# HIVE_BOARD_ETHERNET.net
KiCad netlist of a schematic drawn in Altium Designer
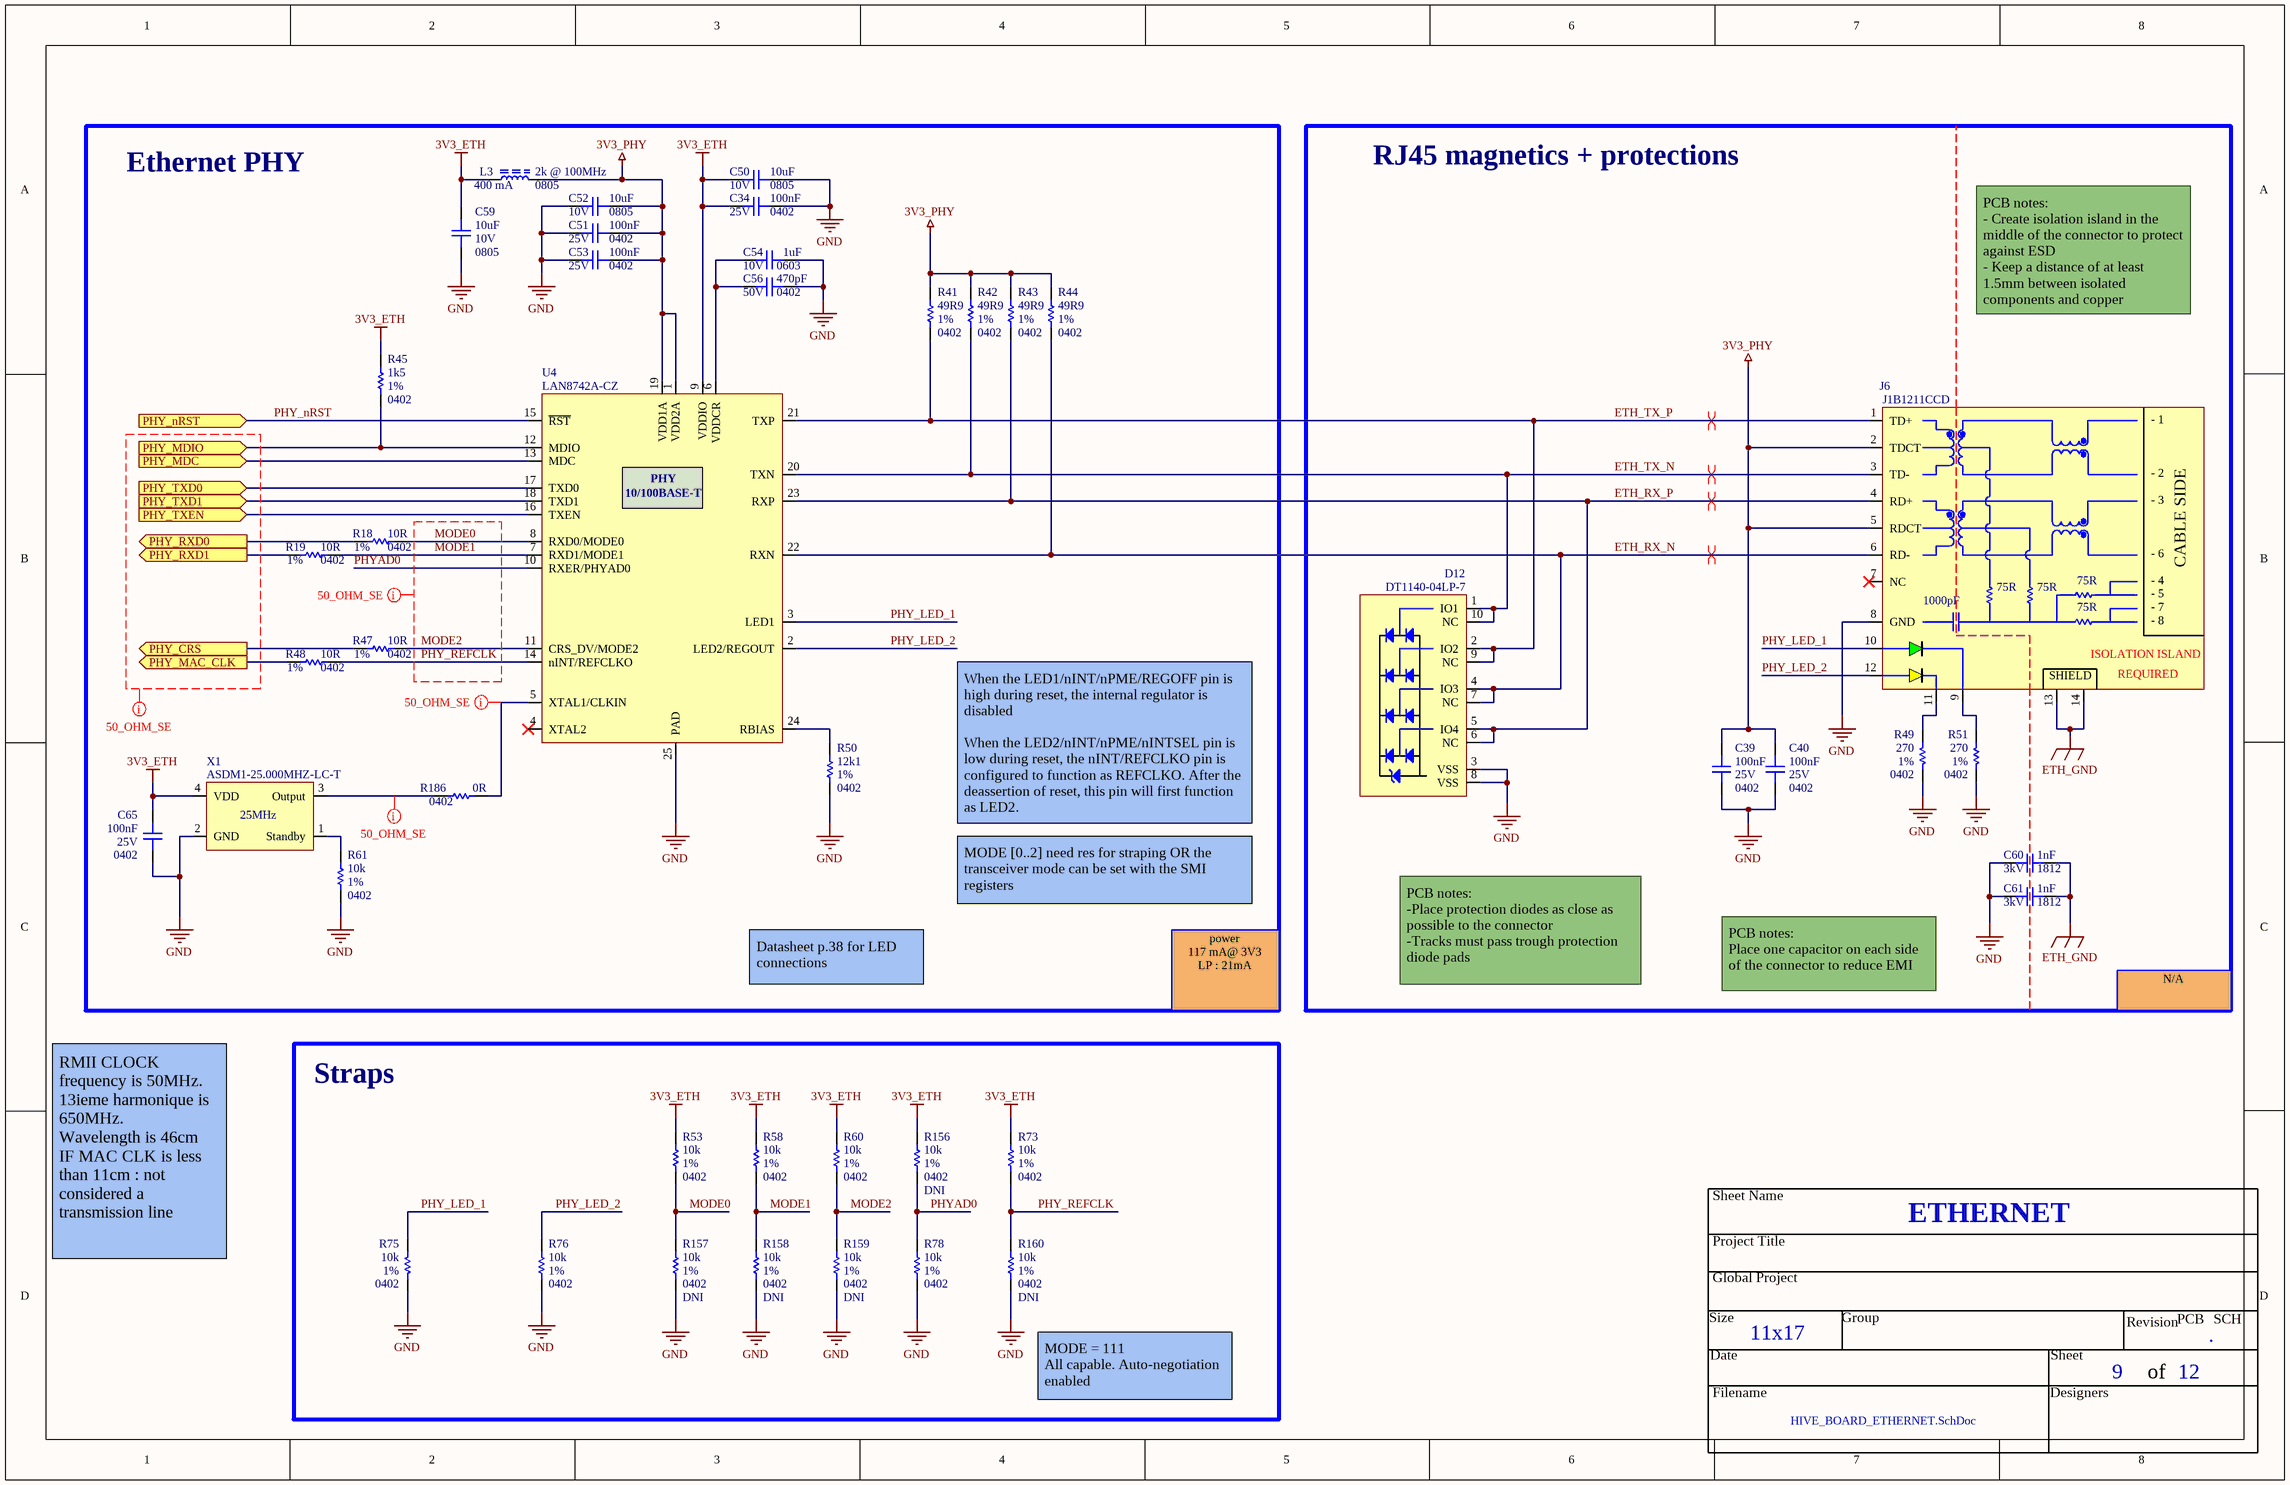
[diagram p0: HIVE_BOARD_ETHERNET.SchDoc]

(export (version "E")
  (design (tool "Eeschema 10.0.6"))
  (components
    (comp (ref "C34")
      (value "100nF")
      (footprint "CAP_CER_0402")
      (description "CAP - CER 0.1µF 10% 25V X7R - 0402")
      (fields
        (field (name "TOLERANCE") "10%")
        (field (name "PACKAGE") "0402")
        (field (name "VOLTAGE RATING") "25V")
        (field (name "Comment") "CGA2B3X7R1E104K050BB")
        (field (name "CREATEDBY/DATE") "Nicolas Roy 2018-11-07")
        (field (name "VERIFIEDBY") "Nicolas V. (2019-01-22)")
      )
      (libsource (lib "GRAMS_MASTER_LIB") (part "CAP_CER_CGA2B3X7R1E104K050BB"))
    )
    (comp (ref "C39")
      (value "100nF")
      (footprint "CAP_CER_0402")
      (description "CAP - CER 0.1µF 10% 25V X7R - 0402")
      (fields
        (field (name "TOLERANCE") "10%")
        (field (name "PACKAGE") "0402")
        (field (name "VOLTAGE RATING") "25V")
        (field (name "Comment") "CGA2B3X7R1E104K050BB")
        (field (name "CREATEDBY/DATE") "Nicolas Roy 2018-11-07")
        (field (name "VERIFIEDBY") "Nicolas V. (2019-01-22)")
      )
      (libsource (lib "GRAMS_MASTER_LIB") (part "CAP_CER_CGA2B3X7R1E104K050BB"))
    )
    (comp (ref "C40")
      (value "100nF")
      (footprint "CAP_CER_0402")
      (description "CAP - CER 0.1µF 10% 25V X7R - 0402")
      (fields
        (field (name "TOLERANCE") "10%")
        (field (name "PACKAGE") "0402")
        (field (name "VOLTAGE RATING") "25V")
        (field (name "Comment") "CGA2B3X7R1E104K050BB")
        (field (name "CREATEDBY/DATE") "Nicolas Roy 2018-11-07")
        (field (name "VERIFIEDBY") "Nicolas V. (2019-01-22)")
      )
      (libsource (lib "GRAMS_MASTER_LIB") (part "CAP_CER_CGA2B3X7R1E104K050BB"))
    )
    (comp (ref "C50")
      (value "10uF")
      (footprint "CAP_CER_0805")
      (description "CAP - CER 10UF 10% 10V X5R - 0805")
      (fields
        (field (name "TOLERANCE") "10%")
        (field (name "PACKAGE") "0805")
        (field (name "VOLTAGE RATING") "10V")
        (field (name "Comment") "LMK212BJ106KG-T")
        (field (name "CREATEDBY/DATE") "Caroline Paulin / 25 juillet 2018")
        (field (name "VERIFIEDBY") "Nicolas V. (2019-01-22)")
      )
      (libsource (lib "GRAMS_MASTER_LIB") (part "CAP_CER_LMK212BJ106KG-T"))
    )
    (comp (ref "C51")
      (value "100nF")
      (footprint "CAP_CER_0402")
      (description "CAP - CER 0.1µF 10% 25V X7R - 0402")
      (fields
        (field (name "TOLERANCE") "10%")
        (field (name "PACKAGE") "0402")
        (field (name "VOLTAGE RATING") "25V")
        (field (name "Comment") "CGA2B3X7R1E104K050BB")
        (field (name "CREATEDBY/DATE") "Nicolas Roy 2018-11-07")
        (field (name "VERIFIEDBY") "Nicolas V. (2019-01-22)")
      )
      (libsource (lib "GRAMS_MASTER_LIB") (part "CAP_CER_CGA2B3X7R1E104K050BB"))
    )
    (comp (ref "C52")
      (value "10uF")
      (footprint "CAP_CER_0805")
      (description "CAP - CER 10UF 10% 10V X5R - 0805")
      (fields
        (field (name "TOLERANCE") "10%")
        (field (name "PACKAGE") "0805")
        (field (name "VOLTAGE RATING") "10V")
        (field (name "Comment") "LMK212BJ106KG-T")
        (field (name "CREATEDBY/DATE") "Caroline Paulin / 25 juillet 2018")
        (field (name "VERIFIEDBY") "Nicolas V. (2019-01-22)")
      )
      (libsource (lib "GRAMS_MASTER_LIB") (part "CAP_CER_LMK212BJ106KG-T"))
    )
    (comp (ref "C53")
      (value "100nF")
      (footprint "CAP_CER_0402")
      (description "CAP - CER 0.1µF 10% 25V X7R - 0402")
      (fields
        (field (name "TOLERANCE") "10%")
        (field (name "PACKAGE") "0402")
        (field (name "VOLTAGE RATING") "25V")
        (field (name "Comment") "CGA2B3X7R1E104K050BB")
        (field (name "CREATEDBY/DATE") "Nicolas Roy 2018-11-07")
        (field (name "VERIFIEDBY") "Nicolas V. (2019-01-22)")
      )
      (libsource (lib "GRAMS_MASTER_LIB") (part "CAP_CER_CGA2B3X7R1E104K050BB"))
    )
    (comp (ref "C54")
      (value "1uF")
      (footprint "CAP_CER_0603")
      (description "CAP - CER 1uF 10V 10% X5R - 0603")
      (fields
        (field (name "TOLERANCE") "10%")
        (field (name "PACKAGE") "0603")
        (field (name "VOLTAGE RATING") "10V")
        (field (name "Comment") "C0603C105K8PACTU")
        (field (name "CREATEDBY/DATE") "Hubert Dube - 21/07/20")
        (field (name "VERIFIEDBY") "Louis-Daniel Gaulin - 21/07/20")
      )
      (libsource (lib "SWARMUS_LIB") (part "CAP_CER_C0603C105K8PACTU"))
    )
    (comp (ref "C56")
      (value "470pF")
      (footprint "CAP_CER_0402")
      (description "CAP - CER 470pF 10% 50V X7R - 0402")
      (fields
        (field (name "TOLERANCE") "10%")
        (field (name "PACKAGE") "0402")
        (field (name "VOLTAGE RATING") "50V")
        (field (name "Comment") "CC0402KRX7R9BB471")
        (field (name "CREATEDBY/DATE") "Nicolas Roy 2018-10-17")
        (field (name "VERIFIEDBY") "Caroline Paulin - 18 janv 2019")
      )
      (libsource (lib "GRAMS_MASTER_LIB") (part "CAP_CER_CC0402KRX7R9BB471"))
    )
    (comp (ref "C59")
      (value "10uF")
      (footprint "CAP_CER_0805")
      (description "CAP - CER 10UF 10% 10V X5R - 0805")
      (fields
        (field (name "TOLERANCE") "10%")
        (field (name "PACKAGE") "0805")
        (field (name "VOLTAGE RATING") "10V")
        (field (name "Comment") "LMK212BJ106KG-T")
        (field (name "CREATEDBY/DATE") "Caroline Paulin / 25 juillet 2018")
        (field (name "VERIFIEDBY") "Nicolas V. (2019-01-22)")
      )
      (libsource (lib "GRAMS_MASTER_LIB") (part "CAP_CER_LMK212BJ106KG-T"))
    )
    (comp (ref "C60")
      (value "1nF")
      (footprint "CAP_CER_1812")
      (description "CAP - CER 1000pF ±10% 3000V X7R")
      (fields
        (field (name "TOLERANCE") "10%")
        (field (name "PACKAGE") "1812")
        (field (name "VOLTAGE RATING") "3kV")
        (field (name "Comment") "885342211009")
        (field (name "CREATEDBY/DATE") "Hubert Dube - 03/02/2021")
        (field (name "VERIFIEDBY") "Philippe Asenault - 08-02-2021")
      )
      (libsource (lib "SWARMUS_LIB") (part "CAP_CER_885342211009"))
    )
    (comp (ref "C61")
      (value "1nF")
      (footprint "CAP_CER_1812")
      (description "CAP - CER 1000pF ±10% 3000V X7R")
      (fields
        (field (name "TOLERANCE") "10%")
        (field (name "PACKAGE") "1812")
        (field (name "VOLTAGE RATING") "3kV")
        (field (name "Comment") "885342211009")
        (field (name "CREATEDBY/DATE") "Hubert Dube - 03/02/2021")
        (field (name "VERIFIEDBY") "Philippe Asenault - 08-02-2021")
      )
      (libsource (lib "SWARMUS_LIB") (part "CAP_CER_885342211009"))
    )
    (comp (ref "C65")
      (value "100nF")
      (footprint "CAP_CER_0402")
      (description "CAP - CER 0.1µF 10% 25V X7R - 0402")
      (fields
        (field (name "TOLERANCE") "10%")
        (field (name "PACKAGE") "0402")
        (field (name "VOLTAGE RATING") "25V")
        (field (name "Comment") "CGA2B3X7R1E104K050BB")
        (field (name "CREATEDBY/DATE") "Nicolas Roy 2018-11-07")
        (field (name "VERIFIEDBY") "Nicolas V. (2019-01-22)")
      )
      (libsource (lib "GRAMS_MASTER_LIB") (part "CAP_CER_CGA2B3X7R1E104K050BB"))
    )
    (comp (ref "D12")
      (value "DT1140-04LP-7")
      (footprint "TVS_DATA_DT1140-04LP-7")
      (description "TVS - DIODE 5.5V 10V - 10-UFDFN")
      (fields
        (field (name "CREATEDBY/DATE") "Joël Lemay 2019-11-20")
        (field (name "VERIFIEDBY") "C.Paulin - 21/11/2019")
      )
      (libsource (lib "GRAMS_MASTER_LIB") (part "TVS_DATA_DT1140-04LP-7"))
    )
    (comp (ref "J6")
      (value "J1B1211CCD")
      (footprint "CON_ETH_J1B1211CCD_WIZ")
      (fields
        (field (name "CREATEDBY/DATE") "Hubert Dube - 12/02/2021")
        (field (name "VERIFIEDBY") "Philippe Arsenault - 2021-03-10")
      )
      (libsource (lib "SWARMUS_LIB") (part "CON_ETH_J1B1211CCD"))
    )
    (comp (ref "L3")
      (value "2k @ 100MHz")
      (footprint "FER_0805")
      (description "FER - FERRITE BEAD 2 KOHM @ 100 MHz 400 mA - 0805")
      (fields
        (field (name "CURRENT RATING") "400 mA")
        (field (name "PACKAGE") "0805")
        (field (name "Comment") "MMZ2012Y202BT000")
        (field (name "CREATEDBY/DATE") "Hubert Dube - 7/02/2021")
        (field (name "VERIFIEDBY") "Philippe Arsenault/ 2021-03-13")
      )
      (libsource (lib "SWARMUS_LIB") (part "FER_MMZ2012Y202BT000"))
    )
    (comp (ref "R18")
      (value "10R")
      (footprint "RES_0402")
      (description "RES - 10R 1% 1/16W - 0402")
      (fields
        (field (name "TOLERANCE") "1%")
        (field (name "PACKAGE") "0402")
        (field (name "Comment") "RMCF0402FT10R0")
        (field (name "CREATEDBY/DATE") "Joel Lemay 2018-07-04")
        (field (name "VERIFIEDBY") "Caroline Paulin - 6 sept 2018")
      )
      (libsource (lib "GRAMS_MASTER_LIB") (part "RES_RMCF0402FT10R0"))
    )
    (comp (ref "R19")
      (value "10R")
      (footprint "RES_0402")
      (description "RES - 10R 1% 1/16W - 0402")
      (fields
        (field (name "TOLERANCE") "1%")
        (field (name "PACKAGE") "0402")
        (field (name "Comment") "RMCF0402FT10R0")
        (field (name "CREATEDBY/DATE") "Joel Lemay 2018-07-04")
        (field (name "VERIFIEDBY") "Caroline Paulin - 6 sept 2018")
      )
      (libsource (lib "GRAMS_MASTER_LIB") (part "RES_RMCF0402FT10R0"))
    )
    (comp (ref "R41")
      (value "49R9")
      (footprint "RES_0402")
      (description "RES - 49.9 R ±1% 1/16W -  0402")
      (fields
        (field (name "TOLERANCE") "1%")
        (field (name "PACKAGE") "0402")
        (field (name "Comment") "RC0402FR-0749R9L")
        (field (name "CREATEDBY/DATE") "Hubert Dubé - 3/02/2020")
        (field (name "VERIFIEDBY") "Philippe Arsenault/2021-02-08")
      )
      (libsource (lib "SWARMUS_LIB") (part "RES_RC0402FR-0749R9L"))
    )
    (comp (ref "R42")
      (value "49R9")
      (footprint "RES_0402")
      (description "RES - 49.9 R ±1% 1/16W -  0402")
      (fields
        (field (name "TOLERANCE") "1%")
        (field (name "PACKAGE") "0402")
        (field (name "Comment") "RC0402FR-0749R9L")
        (field (name "CREATEDBY/DATE") "Hubert Dubé - 3/02/2020")
        (field (name "VERIFIEDBY") "Philippe Arsenault/2021-02-08")
      )
      (libsource (lib "SWARMUS_LIB") (part "RES_RC0402FR-0749R9L"))
    )
    (comp (ref "R43")
      (value "49R9")
      (footprint "RES_0402")
      (description "RES - 49.9 R ±1% 1/16W -  0402")
      (fields
        (field (name "TOLERANCE") "1%")
        (field (name "PACKAGE") "0402")
        (field (name "Comment") "RC0402FR-0749R9L")
        (field (name "CREATEDBY/DATE") "Hubert Dubé - 3/02/2020")
        (field (name "VERIFIEDBY") "Philippe Arsenault/2021-02-08")
      )
      (libsource (lib "SWARMUS_LIB") (part "RES_RC0402FR-0749R9L"))
    )
    (comp (ref "R44")
      (value "49R9")
      (footprint "RES_0402")
      (description "RES - 49.9 R ±1% 1/16W -  0402")
      (fields
        (field (name "TOLERANCE") "1%")
        (field (name "PACKAGE") "0402")
        (field (name "Comment") "RC0402FR-0749R9L")
        (field (name "CREATEDBY/DATE") "Hubert Dubé - 3/02/2020")
        (field (name "VERIFIEDBY") "Philippe Arsenault/2021-02-08")
      )
      (libsource (lib "SWARMUS_LIB") (part "RES_RC0402FR-0749R9L"))
    )
    (comp (ref "R45")
      (value "1k5")
      (footprint "RES_0402")
      (description "RES - 1.5K 1% 1/16W - 0402")
      (fields
        (field (name "TOLERANCE") "1%")
        (field (name "PACKAGE") "0402")
        (field (name "Comment") "RC0402FR-071K5L")
        (field (name "CREATEDBY/DATE") "Philippe Arsenault/21 Janvier 2020")
        (field (name "VERIFIEDBY") "C.Paulin - 28/01/2020")
      )
      (libsource (lib "GRAMS_MASTER_LIB") (part "RES_RC0402FR-071K5L"))
    )
    (comp (ref "R47")
      (value "10R")
      (footprint "RES_0402")
      (description "RES - 10R 1% 1/16W - 0402")
      (fields
        (field (name "TOLERANCE") "1%")
        (field (name "PACKAGE") "0402")
        (field (name "Comment") "RMCF0402FT10R0")
        (field (name "CREATEDBY/DATE") "Joel Lemay 2018-07-04")
        (field (name "VERIFIEDBY") "Caroline Paulin - 6 sept 2018")
      )
      (libsource (lib "GRAMS_MASTER_LIB") (part "RES_RMCF0402FT10R0"))
    )
    (comp (ref "R48")
      (value "10R")
      (footprint "RES_0402")
      (description "RES - 10R 1% 1/16W - 0402")
      (fields
        (field (name "TOLERANCE") "1%")
        (field (name "PACKAGE") "0402")
        (field (name "Comment") "RMCF0402FT10R0")
        (field (name "CREATEDBY/DATE") "Joel Lemay 2018-07-04")
        (field (name "VERIFIEDBY") "Caroline Paulin - 6 sept 2018")
      )
      (libsource (lib "GRAMS_MASTER_LIB") (part "RES_RMCF0402FT10R0"))
    )
    (comp (ref "R49")
      (value "270")
      (footprint "FER_0402")
      (description "RES - 270R 1% 1/16W - 0402")
      (fields
        (field (name "TOLERANCE") "1%")
        (field (name "PACKAGE") "0402")
        (field (name "Comment") "RC0402FR-07270RL")
        (field (name "CREATEDBY/DATE") "Philippe Arsenault 2020-07-24")
        (field (name "VERIFIEDBY") "Louis-Daniel Gaulin / 03-10-2020")
      )
      (libsource (lib "SWARMUS_LIB") (part "RES_RC0402FR-07270RL"))
    )
    (comp (ref "R50")
      (value "12k1")
      (footprint "RES_0402")
      (description "RES - 12K1 ±1% 1/16W - 0402")
      (fields
        (field (name "TOLERANCE") "1%")
        (field (name "PACKAGE") "0402")
        (field (name "Comment") "RC0402FR-0712K1L")
        (field (name "CREATEDBY/DATE") "Hubert Dubé - 7/02/2020")
        (field (name "VERIFIEDBY") "Philippe Arsenault/2021-02-08")
      )
      (libsource (lib "SWARMUS_LIB") (part "RES_RC0402FR-0712K1L"))
    )
    (comp (ref "R51")
      (value "270")
      (footprint "FER_0402")
      (description "RES - 270R 1% 1/16W - 0402")
      (fields
        (field (name "TOLERANCE") "1%")
        (field (name "PACKAGE") "0402")
        (field (name "Comment") "RC0402FR-07270RL")
        (field (name "CREATEDBY/DATE") "Philippe Arsenault 2020-07-24")
        (field (name "VERIFIEDBY") "Louis-Daniel Gaulin / 03-10-2020")
      )
      (libsource (lib "SWARMUS_LIB") (part "RES_RC0402FR-07270RL"))
    )
    (comp (ref "R53")
      (value "10k")
      (footprint "RES_0402")
      (description "RES - 10K OHMS 1% 1/16W - 0402")
      (fields
        (field (name "TOLERANCE") "1%")
        (field (name "PACKAGE") "0402")
        (field (name "Comment") "RC0402FR-0710KL")
        (field (name "CREATEDBY/DATE") "Nicolas V. (2018-11-20)")
        (field (name "VERIFIEDBY") "Nicolas V. (2018-11-20)")
      )
      (libsource (lib "GRAMS_MASTER_LIB") (part "RES_RC0402FR-0710KL"))
    )
    (comp (ref "R58")
      (value "10k")
      (footprint "RES_0402")
      (description "RES - 10K OHMS 1% 1/16W - 0402")
      (fields
        (field (name "TOLERANCE") "1%")
        (field (name "PACKAGE") "0402")
        (field (name "Comment") "RC0402FR-0710KL")
        (field (name "CREATEDBY/DATE") "Nicolas V. (2018-11-20)")
        (field (name "VERIFIEDBY") "Nicolas V. (2018-11-20)")
      )
      (libsource (lib "GRAMS_MASTER_LIB") (part "RES_RC0402FR-0710KL"))
    )
    (comp (ref "R60")
      (value "10k")
      (footprint "RES_0402")
      (description "RES - 10K OHMS 1% 1/16W - 0402")
      (fields
        (field (name "TOLERANCE") "1%")
        (field (name "PACKAGE") "0402")
        (field (name "Comment") "RC0402FR-0710KL")
        (field (name "CREATEDBY/DATE") "Nicolas V. (2018-11-20)")
        (field (name "VERIFIEDBY") "Nicolas V. (2018-11-20)")
      )
      (libsource (lib "GRAMS_MASTER_LIB") (part "RES_RC0402FR-0710KL"))
    )
    (comp (ref "R61")
      (value "10k")
      (footprint "RES_0402")
      (description "RES - 10K OHMS 1% 1/16W - 0402")
      (fields
        (field (name "TOLERANCE") "1%")
        (field (name "PACKAGE") "0402")
        (field (name "Comment") "RC0402FR-0710KL")
        (field (name "CREATEDBY/DATE") "Nicolas V. (2018-11-20)")
        (field (name "VERIFIEDBY") "Nicolas V. (2018-11-20)")
      )
      (libsource (lib "GRAMS_MASTER_LIB") (part "RES_RC0402FR-0710KL"))
    )
    (comp (ref "R73")
      (value "10k")
      (footprint "RES_0402")
      (description "RES - 10K OHMS 1% 1/16W - 0402")
      (fields
        (field (name "TOLERANCE") "1%")
        (field (name "PACKAGE") "0402")
        (field (name "Comment") "RC0402FR-0710KL")
        (field (name "CREATEDBY/DATE") "Nicolas V. (2018-11-20)")
        (field (name "VERIFIEDBY") "Nicolas V. (2018-11-20)")
      )
      (libsource (lib "GRAMS_MASTER_LIB") (part "RES_RC0402FR-0710KL"))
    )
    (comp (ref "R75")
      (value "10k")
      (footprint "RES_0402")
      (description "RES - 10K OHMS 1% 1/16W - 0402")
      (fields
        (field (name "TOLERANCE") "1%")
        (field (name "PACKAGE") "0402")
        (field (name "Comment") "RC0402FR-0710KL")
        (field (name "CREATEDBY/DATE") "Nicolas V. (2018-11-20)")
        (field (name "VERIFIEDBY") "Nicolas V. (2018-11-20)")
      )
      (libsource (lib "GRAMS_MASTER_LIB") (part "RES_RC0402FR-0710KL"))
    )
    (comp (ref "R76")
      (value "10k")
      (footprint "RES_0402")
      (description "RES - 10K OHMS 1% 1/16W - 0402")
      (fields
        (field (name "TOLERANCE") "1%")
        (field (name "PACKAGE") "0402")
        (field (name "Comment") "RC0402FR-0710KL")
        (field (name "CREATEDBY/DATE") "Nicolas V. (2018-11-20)")
        (field (name "VERIFIEDBY") "Nicolas V. (2018-11-20)")
      )
      (libsource (lib "GRAMS_MASTER_LIB") (part "RES_RC0402FR-0710KL"))
    )
    (comp (ref "R78")
      (value "10k")
      (footprint "RES_0402")
      (description "RES - 10K OHMS 1% 1/16W - 0402")
      (fields
        (field (name "TOLERANCE") "1%")
        (field (name "PACKAGE") "0402")
        (field (name "Comment") "RC0402FR-0710KL")
        (field (name "CREATEDBY/DATE") "Nicolas V. (2018-11-20)")
        (field (name "VERIFIEDBY") "Nicolas V. (2018-11-20)")
      )
      (libsource (lib "GRAMS_MASTER_LIB") (part "RES_RC0402FR-0710KL"))
    )
    (comp (ref "R156")
      (value "10k")
      (footprint "RES_0402")
      (description "RES - 10K OHMS 1% 1/16W - 0402")
      (fields
        (field (name "TOLERANCE") "1%")
        (field (name "ASSEMBLY NOTE") "DNI")
        (field (name "PACKAGE") "0402")
        (field (name "Comment") "RC0402FR-0710KL")
        (field (name "CREATEDBY/DATE") "Nicolas V. (2018-11-20)")
        (field (name "VERIFIEDBY") "Nicolas V. (2018-11-20)")
      )
      (libsource (lib "GRAMS_MASTER_LIB") (part "RES_RC0402FR-0710KL"))
    )
    (comp (ref "R157")
      (value "10k")
      (footprint "RES_0402")
      (description "RES - 10K OHMS 1% 1/16W - 0402")
      (fields
        (field (name "TOLERANCE") "1%")
        (field (name "ASSEMBLY NOTE") "DNI")
        (field (name "PACKAGE") "0402")
        (field (name "Comment") "RC0402FR-0710KL")
        (field (name "CREATEDBY/DATE") "Nicolas V. (2018-11-20)")
        (field (name "VERIFIEDBY") "Nicolas V. (2018-11-20)")
      )
      (libsource (lib "GRAMS_MASTER_LIB") (part "RES_RC0402FR-0710KL"))
    )
    (comp (ref "R158")
      (value "10k")
      (footprint "RES_0402")
      (description "RES - 10K OHMS 1% 1/16W - 0402")
      (fields
        (field (name "TOLERANCE") "1%")
        (field (name "ASSEMBLY NOTE") "DNI")
        (field (name "PACKAGE") "0402")
        (field (name "Comment") "RC0402FR-0710KL")
        (field (name "CREATEDBY/DATE") "Nicolas V. (2018-11-20)")
        (field (name "VERIFIEDBY") "Nicolas V. (2018-11-20)")
      )
      (libsource (lib "GRAMS_MASTER_LIB") (part "RES_RC0402FR-0710KL"))
    )
    (comp (ref "R159")
      (value "10k")
      (footprint "RES_0402")
      (description "RES - 10K OHMS 1% 1/16W - 0402")
      (fields
        (field (name "TOLERANCE") "1%")
        (field (name "ASSEMBLY NOTE") "DNI")
        (field (name "PACKAGE") "0402")
        (field (name "Comment") "RC0402FR-0710KL")
        (field (name "CREATEDBY/DATE") "Nicolas V. (2018-11-20)")
        (field (name "VERIFIEDBY") "Nicolas V. (2018-11-20)")
      )
      (libsource (lib "GRAMS_MASTER_LIB") (part "RES_RC0402FR-0710KL"))
    )
    (comp (ref "R160")
      (value "10k")
      (footprint "RES_0402")
      (description "RES - 10K OHMS 1% 1/16W - 0402")
      (fields
        (field (name "TOLERANCE") "1%")
        (field (name "ASSEMBLY NOTE") "DNI")
        (field (name "PACKAGE") "0402")
        (field (name "Comment") "RC0402FR-0710KL")
        (field (name "CREATEDBY/DATE") "Nicolas V. (2018-11-20)")
        (field (name "VERIFIEDBY") "Nicolas V. (2018-11-20)")
      )
      (libsource (lib "GRAMS_MASTER_LIB") (part "RES_RC0402FR-0710KL"))
    )
    (comp (ref "R186")
      (value "0R")
      (footprint "RES_0402")
      (description "RES - 0R 1/16W 1A  - 0402")
      (fields
        (field (name "PACKAGE") "0402")
        (field (name "Comment") "RC0402FR-070RL")
        (field (name "CREATEDBY/DATE") "Keven Deslandes 2018-09-12")
        (field (name "VERIFIEDBY") "Caroline Paulin - 27 fév 2019")
      )
      (libsource (lib "GRAMS_MASTER_LIB") (part "RES_RC0402FR-070RL"))
    )
    (comp (ref "U4")
      (value "LAN8742A-CZ")
      (footprint "COM_ETH_LAN8742A-CZ-TR")
      (description "COM_ETH_ Ethernet PHY 1/1 Transceiver  Ethernet 24-SQFN (4x4) 10/100 BASE-T")
      (fields
        (field (name "VERIFIEDBY") "Philippe Arsenault 2021-03-10")
        (field (name "CREATEDBY/DATE") "Hubert Dube -  28/01/2021")
      )
      (libsource (lib "SWARMUS_LIB") (part "COM_ETH_LAN8742A-CZ"))
    )
    (comp (ref "X1")
      (value "ASDM1-25.000MHZ-LC-T")
      (footprint "OSC_CRY_ASDM1-25.000MHZ-LC-T")
      (description "OSC_CRY - 25MHz +-50ppm LVCMOS Crystal")
      (fields
        (field (name "CREATEDBY/DATE") "Philippe Arsenault/2021-04-07")
        (field (name "VERIFIEDBY") "Louis-Daniel Gaulin / 08-04-2021")
      )
      (libsource (lib "SWARMUS_LIB") (part "OSC_CRY_ASDM1-25.000MHZ-LC-T"))
    )
  )
  (nets
    (net (code "1") (name "/ETH_RX_N") (class "Default")
      (node (ref "D12") (pin "4") (pinfunction "IO3_4") (pintype "passive"))
      (node (ref "D12") (pin "7") (pinfunction "NC_7") (pintype "passive"))
      (node (ref "J6") (pin "6") (pinfunction "RD-_6") (pintype "passive"))
      (node (ref "R44") (pin "1") (pinfunction "1_1") (pintype "passive"))
      (node (ref "U4") (pin "22") (pinfunction "RXN_22") (pintype "passive"))
    )
    (net (code "2") (name "/ETH_RX_P") (class "Default")
      (node (ref "D12") (pin "5") (pinfunction "IO4_5") (pintype "passive"))
      (node (ref "D12") (pin "6") (pinfunction "NC_6") (pintype "passive"))
      (node (ref "J6") (pin "4") (pinfunction "RD+_4") (pintype "passive"))
      (node (ref "R43") (pin "1") (pinfunction "1_1") (pintype "passive"))
      (node (ref "U4") (pin "23") (pinfunction "RXP_23") (pintype "passive"))
    )
    (net (code "3") (name "/ETH_TX_N") (class "Default")
      (node (ref "D12") (pin "1") (pinfunction "IO1_1") (pintype "passive"))
      (node (ref "D12") (pin "10") (pinfunction "NC_10") (pintype "passive"))
      (node (ref "J6") (pin "3") (pinfunction "TD-_3") (pintype "passive"))
      (node (ref "R42") (pin "1") (pinfunction "1_1") (pintype "passive"))
      (node (ref "U4") (pin "20") (pinfunction "TXN_20") (pintype "passive"))
    )
    (net (code "4") (name "/ETH_TX_P") (class "Default")
      (node (ref "D12") (pin "2") (pinfunction "IO2_2") (pintype "passive"))
      (node (ref "D12") (pin "9") (pinfunction "NC_9") (pintype "passive"))
      (node (ref "J6") (pin "1") (pinfunction "TD+_1") (pintype "passive"))
      (node (ref "R41") (pin "1") (pinfunction "1_1") (pintype "passive"))
      (node (ref "U4") (pin "21") (pinfunction "TXP_21") (pintype "passive"))
    )
    (net (code "5") (name "/MODE0") (class "Default")
      (node (ref "R157") (pin "2") (pinfunction "2_2") (pintype "passive"))
      (node (ref "R18") (pin "1") (pinfunction "1_1") (pintype "passive"))
      (node (ref "R53") (pin "1") (pinfunction "1_1") (pintype "passive"))
      (node (ref "U4") (pin "8") (pinfunction "RXD0/MODE0_8") (pintype "passive"))
    )
    (net (code "6") (name "/MODE1") (class "Default")
      (node (ref "R158") (pin "2") (pinfunction "2_2") (pintype "passive"))
      (node (ref "R19") (pin "1") (pinfunction "1_1") (pintype "passive"))
      (node (ref "R58") (pin "1") (pinfunction "1_1") (pintype "passive"))
      (node (ref "U4") (pin "7") (pinfunction "RXD1/MODE1_7") (pintype "passive"))
    )
    (net (code "7") (name "/MODE2") (class "Default")
      (node (ref "R159") (pin "2") (pinfunction "2_2") (pintype "passive"))
      (node (ref "R47") (pin "1") (pinfunction "1_1") (pintype "passive"))
      (node (ref "R60") (pin "1") (pinfunction "1_1") (pintype "passive"))
      (node (ref "U4") (pin "11") (pinfunction "CRS_DV/MODE2_11") (pintype "passive"))
    )
    (net (code "8") (name "/PHYAD0") (class "Default")
      (node (ref "R156") (pin "1") (pinfunction "1_1") (pintype "passive"))
      (node (ref "R78") (pin "2") (pinfunction "2_2") (pintype "passive"))
      (node (ref "U4") (pin "10") (pinfunction "RXER/PHYAD0_10") (pintype "passive"))
    )
    (net (code "9") (name "/PHY_CRS") (class "Default")
      (node (ref "R47") (pin "2") (pinfunction "2_2") (pintype "passive"))
    )
    (net (code "10") (name "/PHY_LED_1") (class "Default")
      (node (ref "J6") (pin "10") (pinfunction "LED1_A_10") (pintype "passive"))
      (node (ref "R75") (pin "2") (pinfunction "2_2") (pintype "passive"))
      (node (ref "U4") (pin "3") (pinfunction "LED1_3") (pintype "passive"))
    )
    (net (code "11") (name "/PHY_LED_2") (class "Default")
      (node (ref "J6") (pin "12") (pintype "passive"))
      (node (ref "R76") (pin "2") (pinfunction "2_2") (pintype "passive"))
      (node (ref "U4") (pin "2") (pinfunction "LED2/REGOUT_2") (pintype "passive"))
    )
    (net (code "12") (name "/PHY_MAC_CLK") (class "Default")
      (node (ref "R48") (pin "2") (pinfunction "2_2") (pintype "passive"))
    )
    (net (code "13") (name "/PHY_MDC") (class "Default")
      (node (ref "U4") (pin "13") (pinfunction "MDC_13") (pintype "passive"))
    )
    (net (code "14") (name "/PHY_MDIO") (class "Default")
      (node (ref "R45") (pin "1") (pinfunction "1_1") (pintype "passive"))
      (node (ref "U4") (pin "12") (pinfunction "MDIO_12") (pintype "passive"))
    )
    (net (code "15") (name "/PHY_REFCLK") (class "Default")
      (node (ref "R160") (pin "2") (pinfunction "2_2") (pintype "passive"))
      (node (ref "R48") (pin "1") (pinfunction "1_1") (pintype "passive"))
      (node (ref "R73") (pin "1") (pinfunction "1_1") (pintype "passive"))
      (node (ref "U4") (pin "14") (pinfunction "nINT/REFCLKO_14") (pintype "passive"))
    )
    (net (code "16") (name "/PHY_RXD0") (class "Default")
      (node (ref "R18") (pin "2") (pinfunction "2_2") (pintype "passive"))
    )
    (net (code "17") (name "/PHY_RXD1") (class "Default")
      (node (ref "R19") (pin "2") (pinfunction "2_2") (pintype "passive"))
    )
    (net (code "18") (name "/PHY_TXD0") (class "Default")
      (node (ref "U4") (pin "17") (pinfunction "TXD0_17") (pintype "passive"))
    )
    (net (code "19") (name "/PHY_TXD1") (class "Default")
      (node (ref "U4") (pin "18") (pinfunction "TXD1_18") (pintype "passive"))
    )
    (net (code "20") (name "/PHY_TXEN") (class "Default")
      (node (ref "U4") (pin "16") (pinfunction "TXEN_16") (pintype "passive"))
    )
    (net (code "21") (name "/PHY_nRST") (class "Default")
      (node (ref "U4") (pin "15") (pinfunction "RST_15") (pintype "passive"))
    )
    (net (code "22") (name "3V3_ETH") (class "Default")
      (node (ref "C34") (pin "2") (pinfunction "2_2") (pintype "passive"))
      (node (ref "C50") (pin "2") (pinfunction "2_2") (pintype "passive"))
      (node (ref "C59") (pin "2") (pinfunction "2_2") (pintype "passive"))
      (node (ref "C65") (pin "1") (pinfunction "1_1") (pintype "passive"))
      (node (ref "L3") (pin "1") (pinfunction "1_1") (pintype "passive"))
      (node (ref "R156") (pin "2") (pinfunction "2_2") (pintype "passive"))
      (node (ref "R45") (pin "2") (pinfunction "2_2") (pintype "passive"))
      (node (ref "R53") (pin "2") (pinfunction "2_2") (pintype "passive"))
      (node (ref "R58") (pin "2") (pinfunction "2_2") (pintype "passive"))
      (node (ref "R60") (pin "2") (pinfunction "2_2") (pintype "passive"))
      (node (ref "R73") (pin "2") (pinfunction "2_2") (pintype "passive"))
      (node (ref "U4") (pin "9") (pinfunction "VDDIO_9") (pintype "passive"))
      (node (ref "X1") (pin "4") (pinfunction "VDD_4") (pintype "passive"))
    )
    (net (code "23") (name "3V3_PHY") (class "Default")
      (node (ref "C39") (pin "1") (pinfunction "1_1") (pintype "passive"))
      (node (ref "C40") (pin "1") (pinfunction "1_1") (pintype "passive"))
      (node (ref "C51") (pin "1") (pinfunction "1_1") (pintype "passive"))
      (node (ref "C52") (pin "1") (pinfunction "1_1") (pintype "passive"))
      (node (ref "C53") (pin "1") (pinfunction "1_1") (pintype "passive"))
      (node (ref "J6") (pin "2") (pinfunction "TDCT_2") (pintype "passive"))
      (node (ref "J6") (pin "5") (pinfunction "RDCT_5") (pintype "passive"))
      (node (ref "L3") (pin "2") (pinfunction "2_2") (pintype "passive"))
      (node (ref "R41") (pin "2") (pinfunction "2_2") (pintype "passive"))
      (node (ref "R42") (pin "2") (pinfunction "2_2") (pintype "passive"))
      (node (ref "R43") (pin "2") (pinfunction "2_2") (pintype "passive"))
      (node (ref "R44") (pin "2") (pinfunction "2_2") (pintype "passive"))
      (node (ref "U4") (pin "1") (pinfunction "VDD2A_1") (pintype "passive"))
      (node (ref "U4") (pin "19") (pinfunction "VDD1A_19") (pintype "passive"))
    )
    (net (code "24") (name "ETH_GND") (class "Default")
      (node (ref "C60") (pin "1") (pinfunction "1_1") (pintype "passive"))
      (node (ref "C61") (pin "1") (pinfunction "1_1") (pintype "passive"))
      (node (ref "J6") (pin "13") (pinfunction "SHIELD_13") (pintype "passive"))
      (node (ref "J6") (pin "14") (pintype "passive"))
    )
    (net (code "25") (name "GND") (class "Default")
      (node (ref "C34") (pin "1") (pinfunction "1_1") (pintype "passive"))
      (node (ref "C39") (pin "2") (pinfunction "2_2") (pintype "passive"))
      (node (ref "C40") (pin "2") (pinfunction "2_2") (pintype "passive"))
      (node (ref "C50") (pin "1") (pinfunction "1_1") (pintype "passive"))
      (node (ref "C51") (pin "2") (pinfunction "2_2") (pintype "passive"))
      (node (ref "C52") (pin "2") (pinfunction "2_2") (pintype "passive"))
      (node (ref "C53") (pin "2") (pinfunction "2_2") (pintype "passive"))
      (node (ref "C54") (pin "1") (pinfunction "1_1") (pintype "passive"))
      (node (ref "C56") (pin "1") (pinfunction "1_1") (pintype "passive"))
      (node (ref "C59") (pin "1") (pinfunction "1_1") (pintype "passive"))
      (node (ref "C60") (pin "2") (pinfunction "2_2") (pintype "passive"))
      (node (ref "C61") (pin "2") (pinfunction "2_2") (pintype "passive"))
      (node (ref "C65") (pin "2") (pinfunction "2_2") (pintype "passive"))
      (node (ref "D12") (pin "3") (pinfunction "VSS_3") (pintype "passive"))
      (node (ref "D12") (pin "8") (pinfunction "VSS_8") (pintype "passive"))
      (node (ref "J6") (pin "8") (pinfunction "GND_8") (pintype "passive"))
      (node (ref "R157") (pin "1") (pinfunction "1_1") (pintype "passive"))
      (node (ref "R158") (pin "1") (pinfunction "1_1") (pintype "passive"))
      (node (ref "R159") (pin "1") (pinfunction "1_1") (pintype "passive"))
      (node (ref "R160") (pin "1") (pinfunction "1_1") (pintype "passive"))
      (node (ref "R49") (pin "1") (pinfunction "1_1") (pintype "passive"))
      (node (ref "R50") (pin "1") (pinfunction "1_1") (pintype "passive"))
      (node (ref "R51") (pin "1") (pinfunction "1_1") (pintype "passive"))
      (node (ref "R61") (pin "1") (pinfunction "1_1") (pintype "passive"))
      (node (ref "R75") (pin "1") (pinfunction "1_1") (pintype "passive"))
      (node (ref "R76") (pin "1") (pinfunction "1_1") (pintype "passive"))
      (node (ref "R78") (pin "1") (pinfunction "1_1") (pintype "passive"))
      (node (ref "U4") (pin "25") (pinfunction "PAD_25") (pintype "passive"))
      (node (ref "X1") (pin "2") (pinfunction "GND_2") (pintype "passive"))
    )
    (net (code "26") (name "Net-(J6-LED1_K)") (class "Default")
      (node (ref "J6") (pin "9") (pinfunction "LED1_K_9") (pintype "passive"))
      (node (ref "R51") (pin "2") (pinfunction "2_2") (pintype "passive"))
    )
    (net (code "27") (name "Net-(J6-Pad11)") (class "Default")
      (node (ref "J6") (pin "11") (pintype "passive"))
      (node (ref "R49") (pin "2") (pinfunction "2_2") (pintype "passive"))
    )
    (net (code "28") (name "Net-(U4-RBIAS)") (class "Default")
      (node (ref "R50") (pin "2") (pinfunction "2_2") (pintype "passive"))
      (node (ref "U4") (pin "24") (pinfunction "RBIAS_24") (pintype "passive"))
    )
    (net (code "29") (name "Net-(U4-VDDCR)") (class "Default")
      (node (ref "C54") (pin "2") (pinfunction "2_2") (pintype "passive"))
      (node (ref "C56") (pin "2") (pinfunction "2_2") (pintype "passive"))
      (node (ref "U4") (pin "6") (pinfunction "VDDCR_6") (pintype "passive"))
    )
    (net (code "30") (name "Net-(U4-XTAL1{slash}CLKIN)") (class "Default")
      (node (ref "R186") (pin "1") (pinfunction "1_1") (pintype "passive"))
      (node (ref "U4") (pin "5") (pinfunction "XTAL1/CLKIN_5") (pintype "passive"))
    )
    (net (code "31") (name "Net-(X1-Output)") (class "Default")
      (node (ref "R186") (pin "2") (pinfunction "2_2") (pintype "passive"))
      (node (ref "X1") (pin "3") (pinfunction "Output_3") (pintype "passive"))
    )
    (net (code "32") (name "Net-(X1-Standby)") (class "Default")
      (node (ref "R61") (pin "2") (pinfunction "2_2") (pintype "passive"))
      (node (ref "X1") (pin "1") (pinfunction "Standby_1") (pintype "passive"))
    )
    (net (code "33") (name "unconnected-(J6-NC-Pad7)") (class "Default")
      (node (ref "J6") (pin "7") (pinfunction "NC_7") (pintype "passive+no_connect"))
    )
    (net (code "34") (name "unconnected-(U4-XTAL2-Pad4)") (class "Default")
      (node (ref "U4") (pin "4") (pinfunction "XTAL2_4") (pintype "passive+no_connect"))
    )
  )
)
